# ESP32_Block.net
KiCad netlist of a schematic drawn in Altium Designer
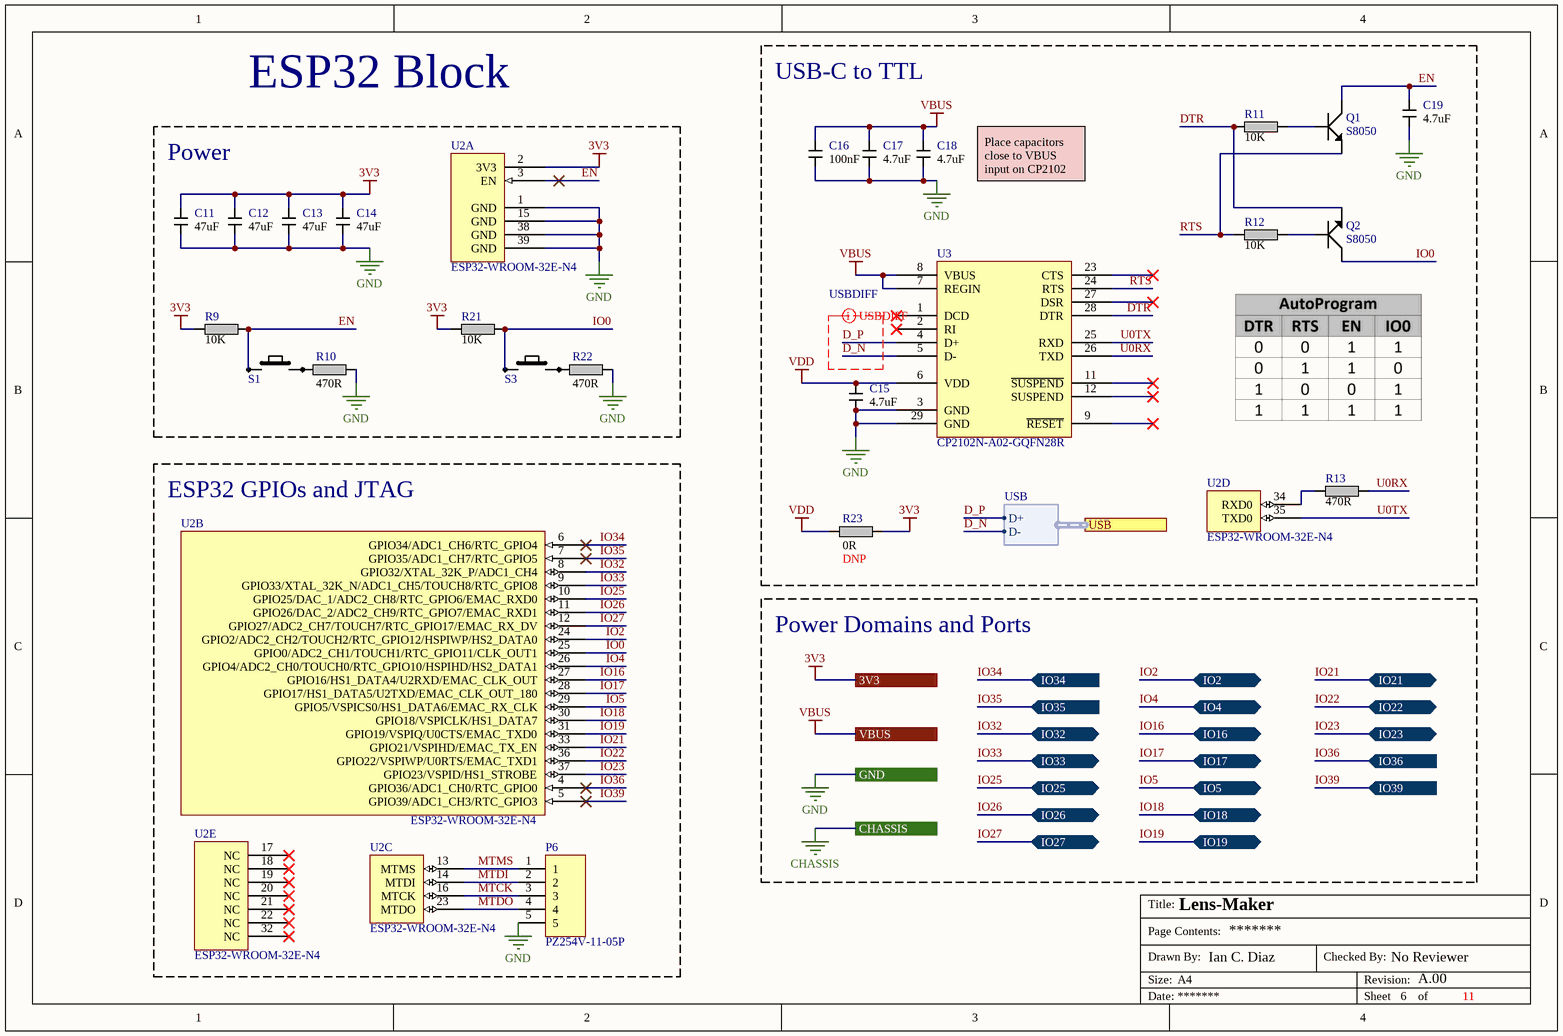
[diagram p0: ESP32_Block.SchDoc]

(export (version "E")
  (design (tool "Eeschema 10.0.6"))
  (components
    (comp (ref "C11")
      (value "47uF")
      (footprint "1206")
      (description "25V 47uF X5R ±20% 1206  Multilayer Ceramic Capacitors MLCC - SMD/SMT ROHS")
      (fields
        (field (name "MANUFACTURER") "TDK")
        (field (name "MANUFACTURER PART NUMBER") "C3216X5R1E476MTJ00E")
      )
      (libsource (lib "Library") (part "CAP"))
    )
    (comp (ref "C12")
      (value "47uF")
      (footprint "1206")
      (description "25V 47uF X5R ±20% 1206  Multilayer Ceramic Capacitors MLCC - SMD/SMT ROHS")
      (fields
        (field (name "MANUFACTURER") "TDK")
        (field (name "MANUFACTURER PART NUMBER") "C3216X5R1E476MTJ00E")
      )
      (libsource (lib "Library") (part "CAP"))
    )
    (comp (ref "C13")
      (value "47uF")
      (footprint "1206")
      (description "25V 47uF X5R ±20% 1206  Multilayer Ceramic Capacitors MLCC - SMD/SMT ROHS")
      (fields
        (field (name "MANUFACTURER") "TDK")
        (field (name "MANUFACTURER PART NUMBER") "C3216X5R1E476MTJ00E")
      )
      (libsource (lib "Library") (part "CAP"))
    )
    (comp (ref "C14")
      (value "47uF")
      (footprint "1206")
      (description "25V 47uF X5R ±20% 1206  Multilayer Ceramic Capacitors MLCC - SMD/SMT ROHS")
      (fields
        (field (name "MANUFACTURER") "TDK")
        (field (name "MANUFACTURER PART NUMBER") "C3216X5R1E476MTJ00E")
      )
      (libsource (lib "Library") (part "CAP"))
    )
    (comp (ref "C15")
      (value "4.7uF")
      (footprint "0805")
      (description "35V 4.7uF X7R ±10% 0805  Multilayer Ceramic Capacitors MLCC - SMD/SMT ROHS")
      (fields
        (field (name "MANUFACTURER") "Samwha Capacitor")
        (field (name "MANUFACTURER PART NUMBER") "CS2012X7R475K350NRE")
      )
      (libsource (lib "Library") (part "CAP"))
    )
    (comp (ref "C16")
      (value "100nF")
      (footprint "0805")
      (description "50V 100nF X7R ±10% 0805  Multilayer Ceramic Capacitors MLCC - SMD/SMT ROHS")
      (fields
        (field (name "MANUFACTURER") "YAGEO")
        (field (name "MANUFACTURER PART NUMBER") "CC0805KRX7R9BB104")
      )
      (libsource (lib "Library") (part "CAP"))
    )
    (comp (ref "C17")
      (value "4.7uF")
      (footprint "0805")
      (description "35V 4.7uF X7R ±10% 0805  Multilayer Ceramic Capacitors MLCC - SMD/SMT ROHS")
      (fields
        (field (name "MANUFACTURER") "Samwha Capacitor")
        (field (name "MANUFACTURER PART NUMBER") "CS2012X7R475K350NRE")
      )
      (libsource (lib "Library") (part "CAP"))
    )
    (comp (ref "C18")
      (value "4.7uF")
      (footprint "0805")
      (description "35V 4.7uF X7R ±10% 0805  Multilayer Ceramic Capacitors MLCC - SMD/SMT ROHS")
      (fields
        (field (name "MANUFACTURER") "Samwha Capacitor")
        (field (name "MANUFACTURER PART NUMBER") "CS2012X7R475K350NRE")
      )
      (libsource (lib "Library") (part "CAP"))
    )
    (comp (ref "C19")
      (value "4.7uF")
      (footprint "0805")
      (description "35V 4.7uF X7R ±10% 0805  Multilayer Ceramic Capacitors MLCC - SMD/SMT ROHS")
      (fields
        (field (name "MANUFACTURER") "Samwha Capacitor")
        (field (name "MANUFACTURER PART NUMBER") "CS2012X7R475K350NRE")
      )
      (libsource (lib "Library") (part "CAP"))
    )
    (comp (ref "P6")
      (value "HEADER-5P-SR")
      (footprint "PZ254V-11-05P")
      (fields (field (name "MANUFACTURER") "XFCN") (field (name "MANUFACTURER PART NUMBER") "PZ254V-11-05P"))
      (libsource (lib "Library") (part "HEADER-5P-SR"))
    )
    (comp (ref "Q1")
      (value "S8050")
      (footprint "SOT-23-3")
      (description "25V 300mW 500mA SOT-23  Bipolar Transistors - BJT ROHS")
      (fields (field (name "MANUFACTURER") "JSMSEMI") (field (name "MANUFACTURER PART NUMBER") "S8050"))
      (libsource (lib "Library") (part "S8050"))
    )
    (comp (ref "Q2")
      (value "S8050")
      (footprint "SOT-23-3")
      (description "25V 300mW 500mA SOT-23  Bipolar Transistors - BJT ROHS")
      (fields (field (name "MANUFACTURER") "JSMSEMI") (field (name "MANUFACTURER PART NUMBER") "S8050"))
      (libsource (lib "Library") (part "S8050"))
    )
    (comp (ref "R9")
      (value "10K")
      (footprint "0805")
      (description "125mW Thick Film Resistors ±1% 10kΩ 0805  Chip Resistor - Surface Mount ROHS")
      (fields
        (field (name "MANUFACTURER") "UNI-ROYAL(Uniroyal Elec)")
        (field (name "MANUFACTURER PART NUMBER") "0805W8F1002T5E")
      )
      (libsource (lib "Library") (part "RES"))
    )
    (comp (ref "R10")
      (value "470R")
      (footprint "0805")
      (description "125mW Thick Film Resistors ±1% 470Ω 0805  Chip Resistor - Surface Mount ROHS")
      (fields
        (field (name "MANUFACTURER") "UNI-ROYAL(Uniroyal Elec)")
        (field (name "MANUFACTURER PART NUMBER") "0805W8F4700T5E")
      )
      (libsource (lib "Library") (part "RES"))
    )
    (comp (ref "R11")
      (value "10K")
      (footprint "0805")
      (description "125mW Thick Film Resistors ±1% 10kΩ 0805  Chip Resistor - Surface Mount ROHS")
      (fields
        (field (name "MANUFACTURER") "UNI-ROYAL(Uniroyal Elec)")
        (field (name "MANUFACTURER PART NUMBER") "0805W8F1002T5E")
      )
      (libsource (lib "Library") (part "RES"))
    )
    (comp (ref "R12")
      (value "10K")
      (footprint "0805")
      (description "125mW Thick Film Resistors ±1% 10kΩ 0805  Chip Resistor - Surface Mount ROHS")
      (fields
        (field (name "MANUFACTURER") "UNI-ROYAL(Uniroyal Elec)")
        (field (name "MANUFACTURER PART NUMBER") "0805W8F1002T5E")
      )
      (libsource (lib "Library") (part "RES"))
    )
    (comp (ref "R13")
      (value "470R")
      (footprint "0805")
      (description "125mW Thick Film Resistors ±1% 470Ω 0805  Chip Resistor - Surface Mount ROHS")
      (fields
        (field (name "MANUFACTURER") "UNI-ROYAL(Uniroyal Elec)")
        (field (name "MANUFACTURER PART NUMBER") "0805W8F4700T5E")
      )
      (libsource (lib "") (part "RES_1"))
    )
    (comp (ref "R21")
      (value "10K")
      (footprint "0805")
      (description "125mW Thick Film Resistors ±1% 10kΩ 0805  Chip Resistor - Surface Mount ROHS")
      (fields
        (field (name "MANUFACTURER") "UNI-ROYAL(Uniroyal Elec)")
        (field (name "MANUFACTURER PART NUMBER") "0805W8F1002T5E")
      )
      (libsource (lib "Library") (part "RES"))
    )
    (comp (ref "R22")
      (value "470R")
      (footprint "0805")
      (description "125mW Thick Film Resistors ±1% 470Ω 0805  Chip Resistor - Surface Mount ROHS")
      (fields
        (field (name "MANUFACTURER") "UNI-ROYAL(Uniroyal Elec)")
        (field (name "MANUFACTURER PART NUMBER") "0805W8F4700T5E")
      )
      (libsource (lib "Library") (part "RES"))
    )
    (comp (ref "R23")
      (value "0R")
      (footprint "0805")
      (description "125mW 0Ω 0805 Chip Resistor - Surface Mount ROHS")
      (fields
        (field (name "MANUFACTURER") "PANASONIC")
        (field (name "MANUFACTURER PART NUMBER") "ERJ6GEY0R00V")
        (field (name "DM") "DNP")
      )
      (libsource (lib "Library") (part "RES"))
    )
    (comp (ref "S1")
      (value "RST")
      (footprint "PUSHBUTTON_2")
      (description "SWITCH TACTILE SPST-NO 0.05A 12V")
      (fields
        (field (name "MANUFACTURER") "C&K")
        (field (name "MANUFACTURER PART NUMBER") "PTS645SM43SMTR92LFS")
      )
      (libsource (lib "Library") (part "PUSHBUTTON_2"))
    )
    (comp (ref "S3")
      (value "BOOT")
      (footprint "PUSHBUTTON_2")
      (description "SWITCH TACTILE SPST-NO 0.05A 12V")
      (fields
        (field (name "MANUFACTURER") "C&K")
        (field (name "MANUFACTURER PART NUMBER") "PTS645SM43SMTR92LFS")
      )
      (libsource (lib "Library") (part "PUSHBUTTON_2"))
    )
    (comp (ref "U2")
      (value "ESP32-WROOM-32E")
      (footprint "ESP32-WROOM-32E")
      (description "RX TXRX MOD WIFI TRACE ANT SMD")
      (fields
        (field (name "MANUFACTURER") "Espressif Systems")
        (field (name "MANUFACTURER PART NUMBER") "ESP32-WROOM-32E-N4")
      )
      (libsource (lib "Library") (part "ESP32-WROOM-32E"))
    )
    (comp (ref "U3")
      (value "CP2102")
      (footprint "CP2102N")
      (description "QFN-28 USB ICs ROHS")
      (fields
        (field (name "MANUFACTURER") "SILICON LABS")
        (field (name "MANUFACTURER PART NUMBER") "CP2102N-A02-GQFN28R")
      )
      (libsource (lib "Library") (part "CP2102"))
    )
  )
  (nets
    (net (code "2") (name "/DTR") (class "Default")
      (node (ref "Q2") (pin "2") (pinfunction "2_2") (pintype "passive"))
      (node (ref "R11") (pin "2") (pinfunction "2_2") (pintype "passive"))
      (node (ref "U3") (pin "28") (pinfunction "DTR_28") (pintype "passive"))
    )
    (net (code "3") (name "/D_N") (class "Default")
      (node (ref "U3") (pin "5") (pinfunction "D-_5") (pintype "passive"))
    )
    (net (code "4") (name "/D_P") (class "Default")
      (node (ref "U3") (pin "4") (pinfunction "D+_4") (pintype "passive"))
    )
    (net (code "5") (name "/EN") (class "Default")
      (node (ref "C19") (pin "1") (pintype "passive"))
      (node (ref "Q1") (pin "3") (pinfunction "3_3") (pintype "passive"))
      (node (ref "R9") (pin "1") (pinfunction "1_1") (pintype "passive"))
      (node (ref "S1") (pin "1") (pinfunction "1_1") (pintype "passive"))
      (node (ref "U2") (pin "3") (pinfunction "EN_3") (pintype "input"))
    )
    (net (code "6") (name "/IO0") (class "Default")
      (node (ref "Q2") (pin "3") (pinfunction "3_3") (pintype "passive"))
      (node (ref "R21") (pin "1") (pinfunction "1_1") (pintype "passive"))
      (node (ref "S3") (pin "1") (pinfunction "1_1") (pintype "passive"))
      (node (ref "U2") (pin "25") (pinfunction "GPIO0/ADC2_CH1/TOUCH1/RTC_GPIO11/CLK_OUT1_25") (pintype "bidirectional"))
    )
    (net (code "7") (name "/IO2") (class "Default")
      (node (ref "U2") (pin "24") (pinfunction "GPIO2/ADC2_CH2/TOUCH2/RTC_GPIO12/HSPIWP/HS2_DATA0_24") (pintype "bidirectional"))
    )
    (net (code "8") (name "/IO4") (class "Default")
      (node (ref "U2") (pin "26") (pinfunction "GPIO4/ADC2_CH0/TOUCH0/RTC_GPIO10/HSPIHD/HS2_DATA1_26") (pintype "bidirectional"))
    )
    (net (code "9") (name "/IO5") (class "Default")
      (node (ref "U2") (pin "29") (pinfunction "GPIO5/VSPICS0/HS1_DATA6/EMAC_RX_CLK_29") (pintype "bidirectional"))
    )
    (net (code "10") (name "/IO16") (class "Default")
      (node (ref "U2") (pin "27") (pinfunction "GPIO16/HS1_DATA4/U2RXD/EMAC_CLK_OUT_27") (pintype "bidirectional"))
    )
    (net (code "11") (name "/IO17") (class "Default")
      (node (ref "U2") (pin "28") (pinfunction "GPIO17/HS1_DATA5/U2TXD/EMAC_CLK_OUT_180_28") (pintype "bidirectional"))
    )
    (net (code "12") (name "/IO18") (class "Default")
      (node (ref "U2") (pin "30") (pinfunction "GPIO18/VSPICLK/HS1_DATA7_30") (pintype "bidirectional"))
    )
    (net (code "13") (name "/IO19") (class "Default")
      (node (ref "U2") (pin "31") (pinfunction "GPIO19/VSPIQ/U0CTS/EMAC_TXD0_31") (pintype "bidirectional"))
    )
    (net (code "14") (name "/IO21") (class "Default")
      (node (ref "U2") (pin "33") (pinfunction "GPIO21/VSPIHD/EMAC_TX_EN_33") (pintype "bidirectional"))
    )
    (net (code "15") (name "/IO22") (class "Default")
      (node (ref "U2") (pin "36") (pinfunction "GPIO22/VSPIWP/U0RTS/EMAC_TXD1_36") (pintype "bidirectional"))
    )
    (net (code "16") (name "/IO23") (class "Default")
      (node (ref "U2") (pin "37") (pinfunction "GPIO23/VSPID/HS1_STROBE_37") (pintype "bidirectional"))
    )
    (net (code "17") (name "/IO25") (class "Default")
      (node (ref "U2") (pin "10") (pinfunction "GPIO25/DAC_1/ADC2_CH8/RTC_GPIO6/EMAC_RXD0_10") (pintype "bidirectional"))
    )
    (net (code "18") (name "/IO26") (class "Default")
      (node (ref "U2") (pin "11") (pinfunction "GPIO26/DAC_2/ADC2_CH9/RTC_GPIO7/EMAC_RXD1_11") (pintype "bidirectional"))
    )
    (net (code "19") (name "/IO27") (class "Default")
      (node (ref "U2") (pin "12") (pinfunction "GPIO27/ADC2_CH7/TOUCH7/RTC_GPIO17/EMAC_RX_DV_12") (pintype "bidirectional"))
    )
    (net (code "20") (name "/IO32") (class "Default")
      (node (ref "U2") (pin "8") (pinfunction "GPIO32/XTAL_32K_P/ADC1_CH4_8") (pintype "bidirectional"))
    )
    (net (code "21") (name "/IO33") (class "Default")
      (node (ref "U2") (pin "9") (pinfunction "GPIO33/XTAL_32K_N/ADC1_CH5/TOUCH8/RTC_GPIO8_9") (pintype "bidirectional"))
    )
    (net (code "22") (name "/IO34") (class "Default")
      (node (ref "U2") (pin "6") (pinfunction "GPIO34/ADC1_CH6/RTC_GPIO4_6") (pintype "input"))
    )
    (net (code "23") (name "/IO35") (class "Default")
      (node (ref "U2") (pin "7") (pinfunction "GPIO35/ADC1_CH7/RTC_GPIO5_7") (pintype "input"))
    )
    (net (code "24") (name "/IO36") (class "Default")
      (node (ref "U2") (pin "4") (pinfunction "GPIO36/ADC1_CH0/RTC_GPIO0_4") (pintype "input"))
    )
    (net (code "25") (name "/IO39") (class "Default")
      (node (ref "U2") (pin "5") (pinfunction "GPIO39/ADC1_CH3/RTC_GPIO3_5") (pintype "input"))
    )
    (net (code "26") (name "/MTCK") (class "Default")
      (node (ref "P6") (pin "3") (pinfunction "3_3") (pintype "passive"))
      (node (ref "U2") (pin "16") (pinfunction "MTCK_16") (pintype "bidirectional"))
    )
    (net (code "27") (name "/MTDI") (class "Default")
      (node (ref "P6") (pin "2") (pinfunction "2_2") (pintype "passive"))
      (node (ref "U2") (pin "14") (pinfunction "MTDI_14") (pintype "bidirectional"))
    )
    (net (code "28") (name "/MTDO") (class "Default")
      (node (ref "P6") (pin "4") (pinfunction "4_4") (pintype "passive"))
      (node (ref "U2") (pin "23") (pinfunction "MTDO_23") (pintype "bidirectional"))
    )
    (net (code "29") (name "/MTMS") (class "Default")
      (node (ref "P6") (pin "1") (pinfunction "1_1") (pintype "passive"))
      (node (ref "U2") (pin "13") (pinfunction "MTMS_13") (pintype "bidirectional"))
    )
    (net (code "30") (name "/RTS") (class "Default")
      (node (ref "Q1") (pin "2") (pinfunction "2_2") (pintype "passive"))
      (node (ref "R12") (pin "2") (pinfunction "2_2") (pintype "passive"))
      (node (ref "U3") (pin "24") (pinfunction "RTS_24") (pintype "passive"))
    )
    (net (code "31") (name "/U0RX") (class "Default")
      (node (ref "R13") (pin "2") (pinfunction "2_2") (pintype "passive"))
      (node (ref "U3") (pin "26") (pinfunction "TXD_26") (pintype "passive"))
    )
    (net (code "32") (name "/U0TX") (class "Default")
      (node (ref "U2") (pin "35") (pinfunction "TXD0_35") (pintype "bidirectional"))
      (node (ref "U3") (pin "25") (pinfunction "RXD_25") (pintype "passive"))
    )
    (net (code "34") (name "3V3") (class "Default")
      (node (ref "C11") (pin "1") (pintype "passive"))
      (node (ref "C12") (pin "1") (pintype "passive"))
      (node (ref "C13") (pin "1") (pintype "passive"))
      (node (ref "C14") (pin "1") (pintype "passive"))
      (node (ref "R21") (pin "2") (pinfunction "2_2") (pintype "passive"))
      (node (ref "R23") (pin "1") (pinfunction "1_1") (pintype "passive"))
      (node (ref "R9") (pin "2") (pinfunction "2_2") (pintype "passive"))
      (node (ref "U2") (pin "2") (pinfunction "3V3_2") (pintype "power_in"))
    )
    (net (code "36") (name "GND") (class "Default")
      (node (ref "C11") (pin "2") (pintype "passive"))
      (node (ref "C12") (pin "2") (pintype "passive"))
      (node (ref "C13") (pin "2") (pintype "passive"))
      (node (ref "C14") (pin "2") (pintype "passive"))
      (node (ref "C15") (pin "2") (pintype "passive"))
      (node (ref "C16") (pin "1") (pintype "passive"))
      (node (ref "C17") (pin "2") (pintype "passive"))
      (node (ref "C18") (pin "2") (pintype "passive"))
      (node (ref "C19") (pin "2") (pintype "passive"))
      (node (ref "P6") (pin "5") (pinfunction "5_5") (pintype "passive"))
      (node (ref "R10") (pin "1") (pinfunction "1_1") (pintype "passive"))
      (node (ref "R22") (pin "1") (pinfunction "1_1") (pintype "passive"))
      (node (ref "U2") (pin "1") (pinfunction "GND_1") (pintype "power_in"))
      (node (ref "U2") (pin "15") (pinfunction "GND_15") (pintype "power_in"))
      (node (ref "U2") (pin "38") (pinfunction "GND_38") (pintype "power_in"))
      (node (ref "U2") (pin "39") (pinfunction "GND_39") (pintype "passive"))
      (node (ref "U3") (pin "29") (pinfunction "GND_29") (pintype "passive"))
      (node (ref "U3") (pin "3") (pinfunction "GND_3") (pintype "passive"))
    )
    (net (code "37") (name "Net-(Q1-Pad1)") (class "Default")
      (node (ref "Q1") (pin "1") (pinfunction "1_1") (pintype "passive"))
      (node (ref "R11") (pin "1") (pinfunction "1_1") (pintype "passive"))
    )
    (net (code "38") (name "Net-(Q2-Pad1)") (class "Default")
      (node (ref "Q2") (pin "1") (pinfunction "1_1") (pintype "passive"))
      (node (ref "R12") (pin "1") (pinfunction "1_1") (pintype "passive"))
    )
    (net (code "39") (name "Net-(R10-Pad2)") (class "Default")
      (node (ref "R10") (pin "2") (pinfunction "2_2") (pintype "passive"))
      (node (ref "S1") (pin "2") (pinfunction "2_2") (pintype "passive"))
    )
    (net (code "40") (name "Net-(R22-Pad2)") (class "Default")
      (node (ref "R22") (pin "2") (pinfunction "2_2") (pintype "passive"))
      (node (ref "S3") (pin "2") (pinfunction "2_2") (pintype "passive"))
    )
    (net (code "41") (name "Net-(U2D-RXD0)") (class "Default")
      (node (ref "R13") (pin "1") (pinfunction "1_1") (pintype "passive"))
      (node (ref "U2") (pin "34") (pinfunction "RXD0_34") (pintype "bidirectional"))
    )
    (net (code "42") (name "VBUS") (class "Default")
      (node (ref "C16") (pin "2") (pintype "passive"))
      (node (ref "C17") (pin "1") (pintype "passive"))
      (node (ref "C18") (pin "1") (pintype "passive"))
      (node (ref "U3") (pin "7") (pinfunction "REGIN_7") (pintype "passive"))
      (node (ref "U3") (pin "8") (pinfunction "VBUS_8") (pintype "passive"))
    )
    (net (code "43") (name "VDD") (class "Default")
      (node (ref "C15") (pin "1") (pintype "passive"))
      (node (ref "R23") (pin "2") (pinfunction "2_2") (pintype "passive"))
      (node (ref "U3") (pin "6") (pinfunction "VDD_6") (pintype "passive"))
    )
    (net (code "44") (name "unconnected-(U2E-NC-Pad17)") (class "Default")
      (node (ref "U2") (pin "17") (pinfunction "NC_17") (pintype "passive+no_connect"))
    )
    (net (code "45") (name "unconnected-(U2E-NC-Pad18)") (class "Default")
      (node (ref "U2") (pin "18") (pinfunction "NC_18") (pintype "passive+no_connect"))
    )
    (net (code "46") (name "unconnected-(U2E-NC-Pad19)") (class "Default")
      (node (ref "U2") (pin "19") (pinfunction "NC_19") (pintype "passive+no_connect"))
    )
    (net (code "47") (name "unconnected-(U2E-NC-Pad20)") (class "Default")
      (node (ref "U2") (pin "20") (pinfunction "NC_20") (pintype "passive+no_connect"))
    )
    (net (code "48") (name "unconnected-(U2E-NC-Pad21)") (class "Default")
      (node (ref "U2") (pin "21") (pinfunction "NC_21") (pintype "passive+no_connect"))
    )
    (net (code "49") (name "unconnected-(U2E-NC-Pad22)") (class "Default")
      (node (ref "U2") (pin "22") (pinfunction "NC_22") (pintype "passive+no_connect"))
    )
    (net (code "50") (name "unconnected-(U2E-NC-Pad32)") (class "Default")
      (node (ref "U2") (pin "32") (pinfunction "NC_32") (pintype "passive+no_connect"))
    )
    (net (code "51") (name "unconnected-(U3-CTS-Pad23)") (class "Default")
      (node (ref "U3") (pin "23") (pinfunction "CTS_23") (pintype "passive+no_connect"))
    )
    (net (code "52") (name "unconnected-(U3-DCD-Pad1)") (class "Default")
      (node (ref "U3") (pin "1") (pinfunction "DCD_1") (pintype "passive+no_connect"))
    )
    (net (code "53") (name "unconnected-(U3-DSR-Pad27)") (class "Default")
      (node (ref "U3") (pin "27") (pinfunction "DSR_27") (pintype "passive+no_connect"))
    )
    (net (code "54") (name "unconnected-(U3-RI-Pad2)") (class "Default")
      (node (ref "U3") (pin "2") (pinfunction "RI_2") (pintype "passive+no_connect"))
    )
    (net (code "55") (name "unconnected-(U3-SUSPEND-Pad12)") (class "Default")
      (node (ref "U3") (pin "12") (pinfunction "SUSPEND_12") (pintype "passive+no_connect"))
    )
    (net (code "56") (name "unconnected-(U3-~{RESET}-Pad9)") (class "Default")
      (node (ref "U3") (pin "9") (pinfunction "~{RESET}_9") (pintype "passive+no_connect"))
    )
    (net (code "57") (name "unconnected-(U3-~{SUSPEND}-Pad11)") (class "Default")
      (node (ref "U3") (pin "11") (pinfunction "~{SUSPEND}_11") (pintype "passive+no_connect"))
    )
  )
)
